# encoder.net
KiCad netlist of a schematic drawn in Altium Designer
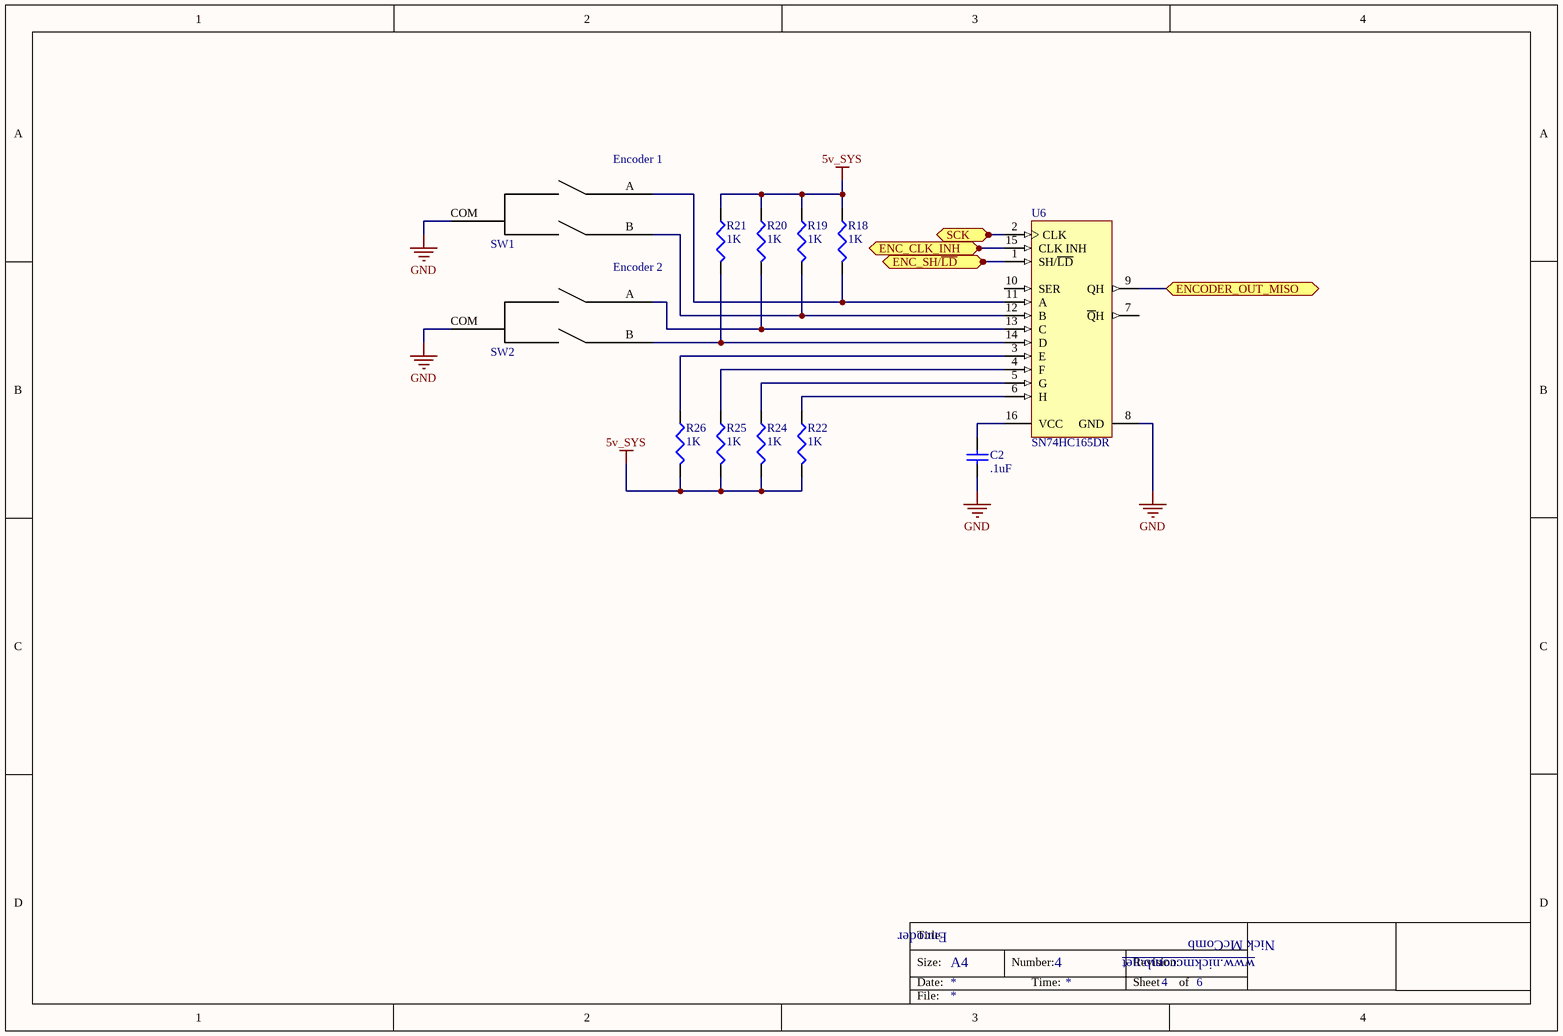
[diagram p0: encoder.SchDoc]

(export (version "E")
  (design (tool "Eeschema 10.0.6"))
  (components
    (comp (ref "C2")
      (value ".1uF")
      (footprint "C0805")
      (description "Capacitor")
      (fields (field (name "Comment") "0805 style, by default") (field (name "PUBLISHER") "Altium Limited"))
      (libsource (lib "lab2") (part "Cap"))
    )
    (comp (ref "R18")
      (value "1K")
      (footprint "J1-0603")
      (description "Resistor")
      (fields (field (name "PUBLISHER") "Altium Limited"))
      (libsource (lib "lab2") (part "Res3"))
    )
    (comp (ref "R19")
      (value "1K")
      (footprint "J1-0603")
      (description "Resistor")
      (fields (field (name "PUBLISHER") "Altium Limited"))
      (libsource (lib "lab2") (part "Res3"))
    )
    (comp (ref "R20")
      (value "1K")
      (footprint "J1-0603")
      (description "Resistor")
      (fields (field (name "PUBLISHER") "Altium Limited"))
      (libsource (lib "lab2") (part "Res3"))
    )
    (comp (ref "R21")
      (value "1K")
      (footprint "J1-0603")
      (description "Resistor")
      (fields (field (name "PUBLISHER") "Altium Limited"))
      (libsource (lib "lab2") (part "Res3"))
    )
    (comp (ref "R22")
      (value "1K")
      (footprint "J1-0603")
      (description "Resistor")
      (fields (field (name "PUBLISHER") "Altium Limited"))
      (libsource (lib "lab2") (part "Res3"))
    )
    (comp (ref "R24")
      (value "1K")
      (footprint "J1-0603")
      (description "Resistor")
      (fields (field (name "PUBLISHER") "Altium Limited"))
      (libsource (lib "lab2") (part "Res3"))
    )
    (comp (ref "R25")
      (value "1K")
      (footprint "J1-0603")
      (description "Resistor")
      (fields (field (name "PUBLISHER") "Altium Limited"))
      (libsource (lib "lab2") (part "Res3"))
    )
    (comp (ref "R26")
      (value "1K")
      (footprint "J1-0603")
      (description "Resistor")
      (fields (field (name "PUBLISHER") "Altium Limited"))
      (libsource (lib "lab2") (part "Res3"))
    )
    (comp (ref "SW1") (value "ENCODER") (libsource (lib "lab2") (part "ENCODER")))
    (comp (ref "SW2") (value "ENCODER") (libsource (lib "lab2") (part "ENCODER")))
    (comp (ref "U6")
      (value "SN74HC165DR")
      (footprint "D0016A_L")
      (description "8-Bit Parallel-Load Shift Registers, D0016A, LARGE T&R")
      (fields (field (name "PART NUMBER") "SN74HC165"))
      (libsource (lib "Altium Content Vault") (part "TI-SNX4XXX165X-16"))
    )
  )
  (nets
    (net (code "1") (name "/ENCODER_OUT_MISO") (class "Default")
      (node (ref "U6") (pin "9") (pinfunction "QH_9") (pintype "output"))
    )
    (net (code "2") (name "/ENC_CLK_INH") (class "Default")
      (node (ref "U6") (pin "15") (pinfunction "CLK_INH_15") (pintype "input"))
    )
    (net (code "3") (name "/ENC_SH{slash}~{LD}") (class "Default")
      (node (ref "U6") (pin "1") (pinfunction "SH/~{LD}_1") (pintype "input"))
    )
    (net (code "4") (name "/SCK") (class "Default")
      (node (ref "U6") (pin "2") (pinfunction "CLK_2") (pintype "input"))
    )
    (net (code "5") (name "5v_SYS") (class "Default")
      (node (ref "R18") (pin "2") (pinfunction "2_2") (pintype "passive"))
      (node (ref "R19") (pin "2") (pinfunction "2_2") (pintype "passive"))
      (node (ref "R20") (pin "2") (pinfunction "2_2") (pintype "passive"))
      (node (ref "R21") (pin "2") (pinfunction "2_2") (pintype "passive"))
      (node (ref "R22") (pin "1") (pinfunction "1_1") (pintype "passive"))
      (node (ref "R24") (pin "1") (pinfunction "1_1") (pintype "passive"))
      (node (ref "R25") (pin "1") (pinfunction "1_1") (pintype "passive"))
      (node (ref "R26") (pin "1") (pinfunction "1_1") (pintype "passive"))
    )
    (net (code "6") (name "GND") (class "Default")
      (node (ref "C2") (pin "1") (pinfunction "1_1") (pintype "passive"))
      (node (ref "SW1") (pin "COM") (pinfunction "COM_COM") (pintype "passive"))
      (node (ref "SW2") (pin "COM") (pinfunction "COM_COM") (pintype "passive"))
      (node (ref "U6") (pin "8") (pinfunction "GND_8") (pintype "power_in"))
    )
    (net (code "7") (name "Net-(U6-A)") (class "Default")
      (node (ref "R18") (pin "1") (pinfunction "1_1") (pintype "passive"))
      (node (ref "SW1") (pin "A") (pinfunction "A_A") (pintype "passive"))
      (node (ref "U6") (pin "11") (pinfunction "A_11") (pintype "input"))
    )
    (net (code "8") (name "Net-(U6-B)") (class "Default")
      (node (ref "R19") (pin "1") (pinfunction "1_1") (pintype "passive"))
      (node (ref "SW1") (pin "B") (pinfunction "B_B") (pintype "passive"))
      (node (ref "U6") (pin "12") (pinfunction "B_12") (pintype "input"))
    )
    (net (code "9") (name "Net-(U6-C)") (class "Default")
      (node (ref "R20") (pin "1") (pinfunction "1_1") (pintype "passive"))
      (node (ref "SW2") (pin "A") (pinfunction "A_A") (pintype "passive"))
      (node (ref "U6") (pin "13") (pinfunction "C_13") (pintype "input"))
    )
    (net (code "10") (name "Net-(U6-D)") (class "Default")
      (node (ref "R21") (pin "1") (pinfunction "1_1") (pintype "passive"))
      (node (ref "SW2") (pin "B") (pinfunction "B_B") (pintype "passive"))
      (node (ref "U6") (pin "14") (pinfunction "D_14") (pintype "input"))
    )
    (net (code "11") (name "Net-(U6-E)") (class "Default")
      (node (ref "R26") (pin "2") (pinfunction "2_2") (pintype "passive"))
      (node (ref "U6") (pin "3") (pinfunction "E_3") (pintype "input"))
    )
    (net (code "12") (name "Net-(U6-F)") (class "Default")
      (node (ref "R25") (pin "2") (pinfunction "2_2") (pintype "passive"))
      (node (ref "U6") (pin "4") (pinfunction "F_4") (pintype "input"))
    )
    (net (code "13") (name "Net-(U6-G)") (class "Default")
      (node (ref "R24") (pin "2") (pinfunction "2_2") (pintype "passive"))
      (node (ref "U6") (pin "5") (pinfunction "G_5") (pintype "input"))
    )
    (net (code "14") (name "Net-(U6-H)") (class "Default")
      (node (ref "R22") (pin "2") (pinfunction "2_2") (pintype "passive"))
      (node (ref "U6") (pin "6") (pinfunction "H_6") (pintype "input"))
    )
    (net (code "15") (name "Net-(U6-VCC)") (class "Default")
      (node (ref "C2") (pin "2") (pinfunction "2_2") (pintype "passive"))
      (node (ref "U6") (pin "16") (pinfunction "VCC_16") (pintype "power_in"))
    )
    (net (code "16") (name "unconnected-(U6-SER-Pad10)") (class "Default")
      (node (ref "U6") (pin "10") (pinfunction "SER_10") (pintype "input"))
    )
    (net (code "17") (name "unconnected-(U6-~{Q}H-Pad7)") (class "Default")
      (node (ref "U6") (pin "7") (pinfunction "~{Q}H_7") (pintype "output"))
    )
  )
)
